# v0_5_0.net
KiCad netlist of a schematic drawn in EAGLE
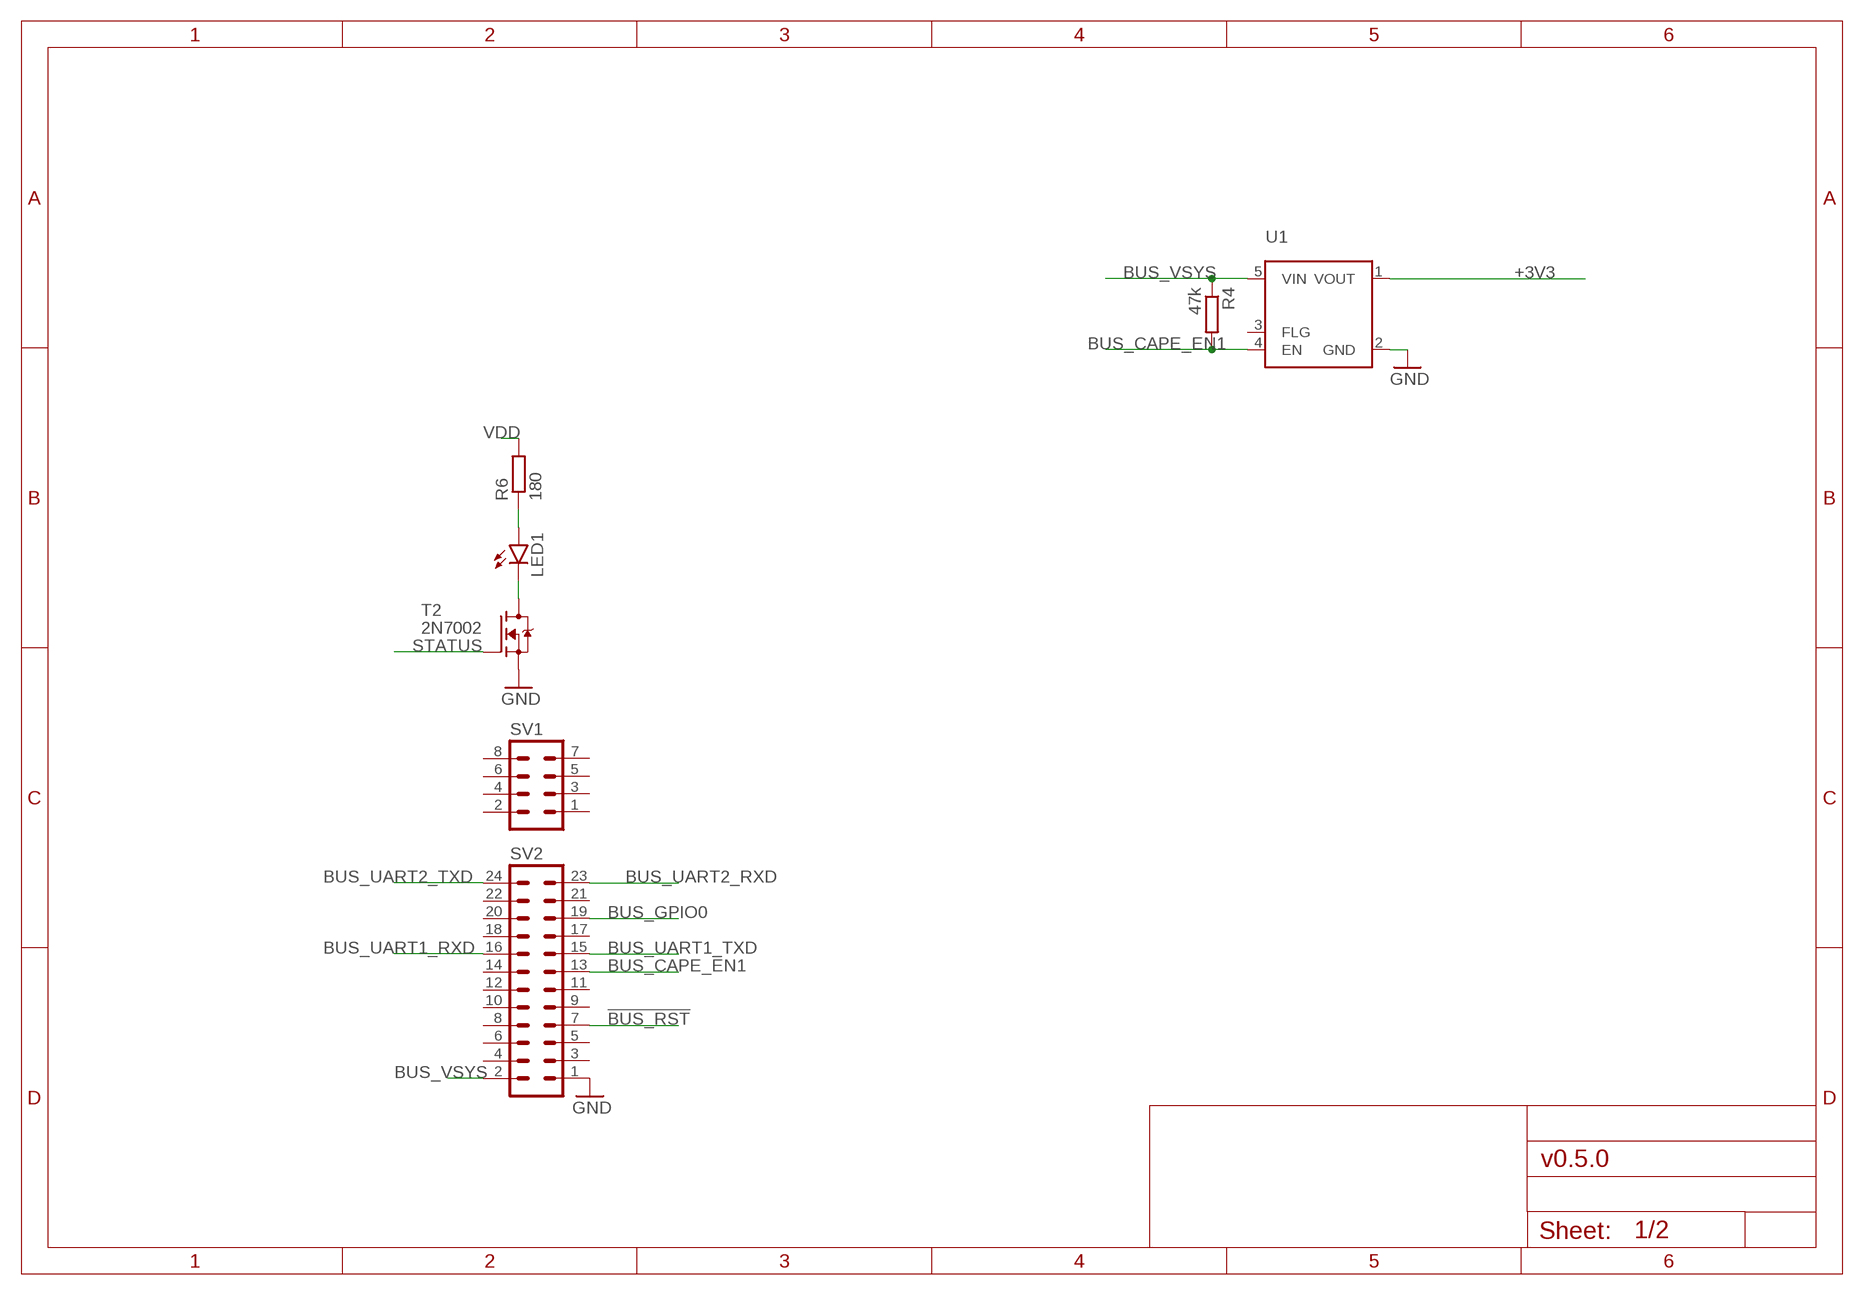
[diagram p0: schematic, sheet 1]
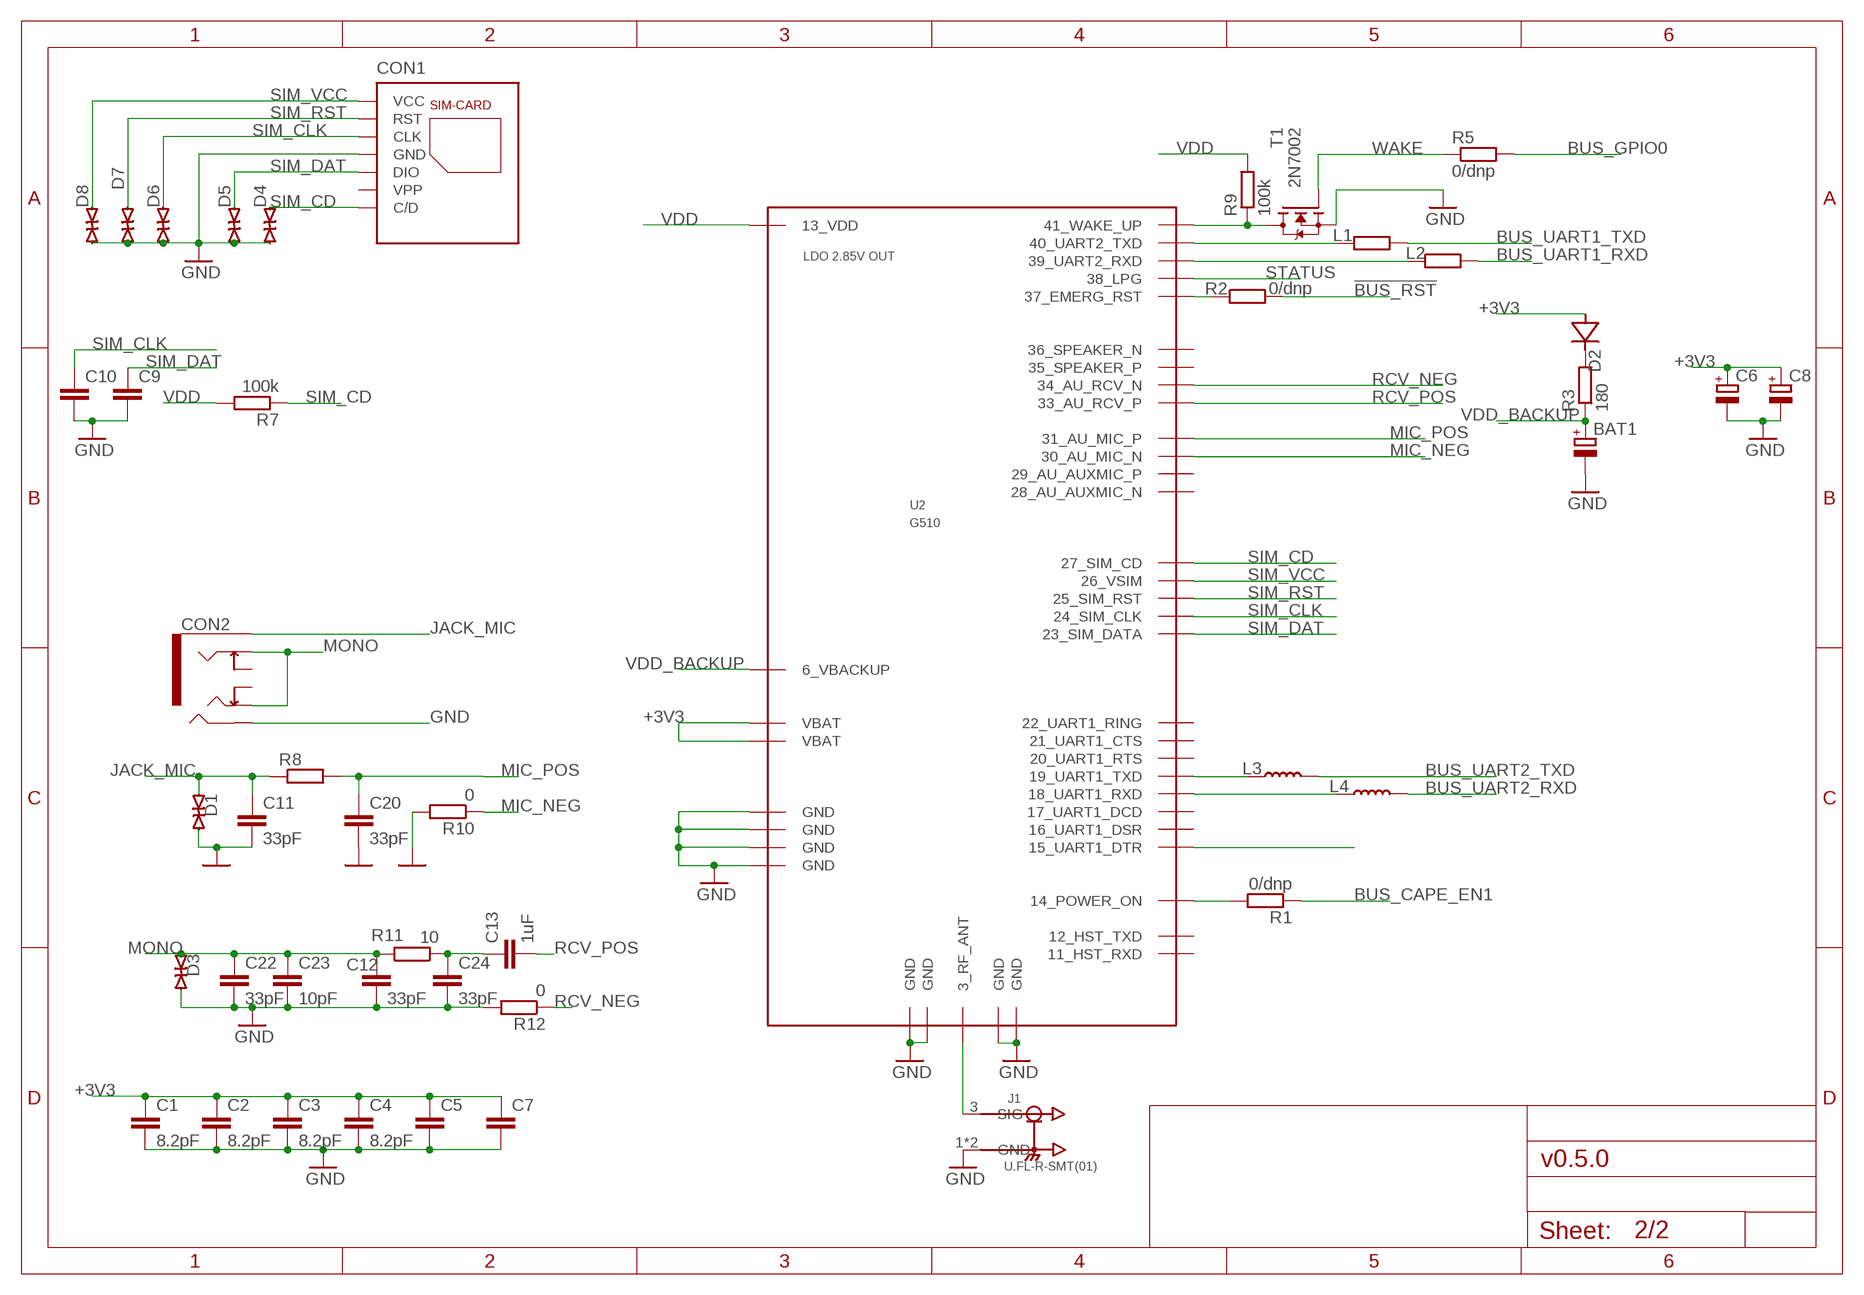
[diagram p1: schematic, sheet 2]

(export (version "E")
  (design (tool "Eeschema 10.0.6"))
  (components
    (comp (ref "LED1")
      (value "LEDCHIP-LED0603")
      (footprint "eagle-import:CHIP-LED0603")
      (libsource (lib "eagle-import") (part "LEDCHIP-LED0603"))
    )
    (comp (ref "R4")
      (value "47k")
      (footprint "eagle-import:R0402")
      (libsource (lib "eagle-import") (part "R-EU_R0402"))
    )
    (comp (ref "R6")
      (value "180")
      (footprint "eagle-import:R0402")
      (libsource (lib "eagle-import") (part "R-EU_R0402"))
    )
    (comp (ref "SV1")
      (value "MA04-2")
      (footprint "eagle-import:MA04-2")
      (libsource (lib "eagle-import") (part "MA04-2"))
    )
    (comp (ref "SV2")
      (value "MA12-2")
      (footprint "eagle-import:MA12-2")
      (libsource (lib "eagle-import") (part "MA12-2"))
    )
    (comp (ref "T2")
      (value "2N7002")
      (footprint "eagle-import:SOT95P240X110-3")
      (libsource (lib "eagle-import") (part "2N7002"))
    )
    (comp (ref "U1")
      (value "ap22802")
      (footprint "eagle-import:SOT25")
      (libsource (lib "eagle-import") (part "AP22802"))
    )
    (comp (ref "BAT1")
      (value "DCK-3R3E224U-E")
      (footprint "eagle-import:621")
      (libsource (lib "eagle-import") (part "DCK-3R3E224U-E"))
    )
    (comp (ref "C1")
      (value "8.2pF")
      (footprint "eagle-import:C0402K")
      (libsource (lib "eagle-import") (part "CAP-0402"))
    )
    (comp (ref "C2")
      (value "8.2pF")
      (footprint "eagle-import:C0402K")
      (libsource (lib "eagle-import") (part "CAP-0402"))
    )
    (comp (ref "C3")
      (value "8.2pF")
      (footprint "eagle-import:C0402K")
      (libsource (lib "eagle-import") (part "CAP-0402"))
    )
    (comp (ref "C4")
      (value "8.2pF")
      (footprint "eagle-import:C0402K")
      (libsource (lib "eagle-import") (part "CAP-0402"))
    )
    (comp (ref "C5")
      (value "C-EUC0603")
      (footprint "eagle-import:C0603")
      (libsource (lib "eagle-import") (part "C-EUC0603"))
    )
    (comp (ref "C6")
      (value "CAP-POL-SMC")
      (footprint "eagle-import:SMC_C")
      (libsource (lib "eagle-import") (part "CAP-POL-SMC"))
    )
    (comp (ref "C7")
      (value "C-EUC0603")
      (footprint "eagle-import:C0603")
      (libsource (lib "eagle-import") (part "C-EUC0603"))
    )
    (comp (ref "C8")
      (value "CAP-POL-SMC")
      (footprint "eagle-import:SMC_C")
      (libsource (lib "eagle-import") (part "CAP-POL-SMC"))
    )
    (comp (ref "C9")
      (value "CAP-0402")
      (footprint "eagle-import:C0402K")
      (libsource (lib "eagle-import") (part "CAP-0402"))
    )
    (comp (ref "C10")
      (value "CAP-0402")
      (footprint "eagle-import:C0402K")
      (libsource (lib "eagle-import") (part "CAP-0402"))
    )
    (comp (ref "C11")
      (value "33pF")
      (footprint "eagle-import:C0402K")
      (libsource (lib "eagle-import") (part "CAP-0402"))
    )
    (comp (ref "C12")
      (value "33pF")
      (footprint "eagle-import:C0402K")
      (libsource (lib "eagle-import") (part "CAP-0402"))
    )
    (comp (ref "C13")
      (value "1uF")
      (footprint "eagle-import:C0402K")
      (libsource (lib "eagle-import") (part "CAP-0402"))
    )
    (comp (ref "C20")
      (value "33pF")
      (footprint "eagle-import:C0402K")
      (libsource (lib "eagle-import") (part "CAP-0402"))
    )
    (comp (ref "C22")
      (value "33pF")
      (footprint "eagle-import:C0402K")
      (libsource (lib "eagle-import") (part "CAP-0402"))
    )
    (comp (ref "C23")
      (value "10pF")
      (footprint "eagle-import:C0402K")
      (libsource (lib "eagle-import") (part "CAP-0402"))
    )
    (comp (ref "C24")
      (value "33pF")
      (footprint "eagle-import:C0402K")
      (libsource (lib "eagle-import") (part "CAP-0402"))
    )
    (comp (ref "CON1")
      (value "115Q-BCA0")
      (footprint "eagle-import:115Q")
      (libsource (lib "eagle-import") (part "115Q-BCA0"))
    )
    (comp (ref "CON2")
      (value "1503-21")
      (footprint "eagle-import:150321")
      (libsource (lib "eagle-import") (part "1503-21"))
    )
    (comp (ref "D1")
      (value "ESD9B5.0ST5G")
      (footprint "eagle-import:SOD1006X40")
      (libsource (lib "eagle-import") (part "ESD9B5.0ST5G"))
    )
    (comp (ref "D2")
      (value "1N4148WS")
      (footprint "eagle-import:SOD323")
      (libsource (lib "eagle-import") (part "1N4148WS"))
    )
    (comp (ref "D3")
      (value "ESD9B5.0ST5G")
      (footprint "eagle-import:SOD1006X40")
      (libsource (lib "eagle-import") (part "ESD9B5.0ST5G"))
    )
    (comp (ref "D4")
      (value "ESD9B5.0ST5G")
      (footprint "eagle-import:SOD1006X40")
      (libsource (lib "eagle-import") (part "ESD9B5.0ST5G"))
    )
    (comp (ref "D5")
      (value "ESD9B5.0ST5G")
      (footprint "eagle-import:SOD1006X40")
      (libsource (lib "eagle-import") (part "ESD9B5.0ST5G"))
    )
    (comp (ref "D6")
      (value "ESD9B5.0ST5G")
      (footprint "eagle-import:SOD1006X40")
      (libsource (lib "eagle-import") (part "ESD9B5.0ST5G"))
    )
    (comp (ref "D7")
      (value "ESD9B5.0ST5G")
      (footprint "eagle-import:SOD1006X40")
      (libsource (lib "eagle-import") (part "ESD9B5.0ST5G"))
    )
    (comp (ref "D8")
      (value "ESD9B5.0ST5G")
      (footprint "eagle-import:SOD1006X40")
      (libsource (lib "eagle-import") (part "ESD9B5.0ST5G"))
    )
    (comp (ref "J1")
      (value "U.FL-R-SMT(01)")
      (footprint "eagle-import:HRS_U.FL-R-SMT(01)")
      (fields (field (name "MF") "Hirose") (field (name "MP") "U.FL-R-SMT_01_"))
      (libsource (lib "eagle-import") (part "U.FL-R-SMT(01)"))
    )
    (comp (ref "L1")
      (value "R-EU_R0402")
      (footprint "eagle-import:R0402")
      (libsource (lib "eagle-import") (part "R-EU_R0402"))
    )
    (comp (ref "L2")
      (value "R-EU_R0402")
      (footprint "eagle-import:R0402")
      (libsource (lib "eagle-import") (part "R-EU_R0402"))
    )
    (comp (ref "L3")
      (value "IND-0402")
      (footprint "eagle-import:L0402")
      (libsource (lib "eagle-import") (part "IND-0402"))
    )
    (comp (ref "L4")
      (value "IND-0402")
      (footprint "eagle-import:L0402")
      (libsource (lib "eagle-import") (part "IND-0402"))
    )
    (comp (ref "R1")
      (value "0/dnp")
      (footprint "eagle-import:R0402")
      (libsource (lib "eagle-import") (part "R-EU_R0402"))
    )
    (comp (ref "R2")
      (value "0/dnp")
      (footprint "eagle-import:R0402")
      (libsource (lib "eagle-import") (part "R-EU_R0402"))
    )
    (comp (ref "R3")
      (value "180")
      (footprint "eagle-import:R0402")
      (libsource (lib "eagle-import") (part "R-EU_R0402"))
    )
    (comp (ref "R5")
      (value "0/dnp")
      (footprint "eagle-import:R0402")
      (libsource (lib "eagle-import") (part "R-EU_R0402"))
    )
    (comp (ref "R7")
      (value "100k")
      (footprint "eagle-import:R0402")
      (libsource (lib "eagle-import") (part "R-EU_R0402"))
    )
    (comp (ref "R8")
      (value "R-EU_R0402")
      (footprint "eagle-import:R0402")
      (libsource (lib "eagle-import") (part "R-EU_R0402"))
    )
    (comp (ref "R9")
      (value "100k")
      (footprint "eagle-import:R0402")
      (libsource (lib "eagle-import") (part "R-EU_R0402"))
    )
    (comp (ref "R10")
      (value "0")
      (footprint "eagle-import:R0402")
      (libsource (lib "eagle-import") (part "R-EU_R0402"))
    )
    (comp (ref "R11")
      (value "10")
      (footprint "eagle-import:R0402")
      (libsource (lib "eagle-import") (part "R-EU_R0402"))
    )
    (comp (ref "R12")
      (value "0")
      (footprint "eagle-import:R0402")
      (libsource (lib "eagle-import") (part "R-EU_R0402"))
    )
    (comp (ref "T1")
      (value "2N7002")
      (footprint "eagle-import:SOT95P240X110-3")
      (libsource (lib "eagle-import") (part "2N7002"))
    )
    (comp (ref "U2")
      (value "G510")
      (footprint "eagle-import:G510")
      (libsource (lib "eagle-import") (part "G510"))
    )
  )
  (nets
    (net (code "1") (name "+3V3") (class "Default")
      (node (ref "C1") (pin "1") (pinfunction "1_1") (pintype "passive"))
      (node (ref "C2") (pin "1") (pinfunction "1_1") (pintype "passive"))
      (node (ref "C3") (pin "1") (pinfunction "1_1") (pintype "passive"))
      (node (ref "C4") (pin "1") (pinfunction "1_1") (pintype "passive"))
      (node (ref "C5") (pin "1") (pinfunction "1_1") (pintype "passive"))
      (node (ref "C6") (pin "+") (pinfunction "+_+") (pintype "passive"))
      (node (ref "C7") (pin "1") (pinfunction "1_1") (pintype "passive"))
      (node (ref "C8") (pin "+") (pinfunction "+_+") (pintype "passive"))
      (node (ref "D2") (pin "A") (pinfunction "A_A") (pintype "passive"))
      (node (ref "U1") (pin "1") (pinfunction "VOUT_1") (pintype "bidirectional"))
      (node (ref "U2") (pin "10_VBAT") (pinfunction "VBAT_10_VBAT") (pintype "power_in"))
      (node (ref "U2") (pin "9_VBAT") (pinfunction "VBAT_9_VBAT") (pintype "power_in"))
    )
    (net (code "2") (name "BUS_CAPE_EN1") (class "Default")
      (node (ref "R1") (pin "1") (pinfunction "1_1") (pintype "passive"))
      (node (ref "R4") (pin "2") (pinfunction "2_2") (pintype "passive"))
      (node (ref "SV2") (pin "13") (pinfunction "13_13") (pintype "passive"))
      (node (ref "U1") (pin "4") (pinfunction "EN_4") (pintype "bidirectional"))
    )
    (net (code "3") (name "BUS_GPIO0") (class "Default")
      (node (ref "R5") (pin "2") (pinfunction "2_2") (pintype "passive"))
      (node (ref "SV2") (pin "19") (pinfunction "19_19") (pintype "passive"))
    )
    (net (code "4") (name "BUS_UART1_RXD") (class "Default")
      (node (ref "L2") (pin "2") (pinfunction "2_2") (pintype "passive"))
      (node (ref "SV2") (pin "16") (pinfunction "16_16") (pintype "passive"))
    )
    (net (code "5") (name "BUS_UART1_TXD") (class "Default")
      (node (ref "L1") (pin "2") (pinfunction "2_2") (pintype "passive"))
      (node (ref "SV2") (pin "15") (pinfunction "15_15") (pintype "passive"))
    )
    (net (code "6") (name "BUS_UART2_RXD") (class "Default")
      (node (ref "L4") (pin "2") (pinfunction "2_2") (pintype "passive"))
      (node (ref "SV2") (pin "23") (pinfunction "23_23") (pintype "passive"))
    )
    (net (code "7") (name "BUS_UART2_TXD") (class "Default")
      (node (ref "L3") (pin "2") (pinfunction "2_2") (pintype "passive"))
      (node (ref "SV2") (pin "24") (pinfunction "24_24") (pintype "passive"))
    )
    (net (code "8") (name "BUS_VSYS") (class "Default")
      (node (ref "R4") (pin "1") (pinfunction "1_1") (pintype "passive"))
      (node (ref "SV2") (pin "2") (pinfunction "2_2") (pintype "passive"))
      (node (ref "U1") (pin "5") (pinfunction "VIN_5") (pintype "bidirectional"))
    )
    (net (code "9") (name "GND") (class "Default")
      (node (ref "BAT1") (pin "-") (pinfunction "-_-") (pintype "passive"))
      (node (ref "C1") (pin "2") (pinfunction "2_2") (pintype "passive"))
      (node (ref "C10") (pin "2") (pinfunction "2_2") (pintype "passive"))
      (node (ref "C11") (pin "2") (pinfunction "2_2") (pintype "passive"))
      (node (ref "C12") (pin "2") (pinfunction "2_2") (pintype "passive"))
      (node (ref "C2") (pin "2") (pinfunction "2_2") (pintype "passive"))
      (node (ref "C20") (pin "2") (pinfunction "2_2") (pintype "passive"))
      (node (ref "C22") (pin "2") (pinfunction "2_2") (pintype "passive"))
      (node (ref "C23") (pin "2") (pinfunction "2_2") (pintype "passive"))
      (node (ref "C24") (pin "2") (pinfunction "2_2") (pintype "passive"))
      (node (ref "C3") (pin "2") (pinfunction "2_2") (pintype "passive"))
      (node (ref "C4") (pin "2") (pinfunction "2_2") (pintype "passive"))
      (node (ref "C5") (pin "2") (pinfunction "2_2") (pintype "passive"))
      (node (ref "C6") (pin "-") (pinfunction "-_-") (pintype "passive"))
      (node (ref "C7") (pin "2") (pinfunction "2_2") (pintype "passive"))
      (node (ref "C8") (pin "-") (pinfunction "-_-") (pintype "passive"))
      (node (ref "C9") (pin "2") (pinfunction "2_2") (pintype "passive"))
      (node (ref "CON1") (pin "GND1") (pinfunction "GND_GND1") (pintype "passive"))
      (node (ref "CON1") (pin "GND2") (pinfunction "GND_GND2") (pintype "passive"))
      (node (ref "CON1") (pin "GND3") (pinfunction "GND_GND3") (pintype "passive"))
      (node (ref "CON1") (pin "GND4") (pinfunction "GND_GND4") (pintype "passive"))
      (node (ref "CON1") (pin "P5") (pinfunction "GND_P5") (pintype "passive"))
      (node (ref "CON2") (pin "2") (pinfunction "2_2") (pintype "bidirectional"))
      (node (ref "D1") (pin "2") (pinfunction "C_2") (pintype "passive"))
      (node (ref "D3") (pin "2") (pinfunction "C_2") (pintype "passive"))
      (node (ref "D4") (pin "1") (pinfunction "A_1") (pintype "passive"))
      (node (ref "D5") (pin "1") (pinfunction "A_1") (pintype "passive"))
      (node (ref "D6") (pin "1") (pinfunction "A_1") (pintype "passive"))
      (node (ref "D7") (pin "1") (pinfunction "A_1") (pintype "passive"))
      (node (ref "D8") (pin "1") (pinfunction "A_1") (pintype "passive"))
      (node (ref "J1") (pin "1") (pinfunction "GND_1") (pintype "passive"))
      (node (ref "J1") (pin "2") (pinfunction "GND_2") (pintype "passive"))
      (node (ref "R10") (pin "2") (pinfunction "2_2") (pintype "passive"))
      (node (ref "R12") (pin "2") (pinfunction "2_2") (pintype "passive"))
      (node (ref "SV2") (pin "1") (pinfunction "1_1") (pintype "passive"))
      (node (ref "T1") (pin "2") (pinfunction "S_2") (pintype "passive"))
      (node (ref "T2") (pin "2") (pinfunction "S_2") (pintype "passive"))
      (node (ref "U1") (pin "2") (pinfunction "GND_2") (pintype "bidirectional"))
      (node (ref "U2") (pin "1_GND") (pinfunction "GND_1_GND") (pintype "power_in"))
      (node (ref "U2") (pin "2_GND") (pinfunction "GND_2_GND") (pintype "power_in"))
      (node (ref "U2") (pin "32_GND") (pinfunction "GND_32_GND") (pintype "power_in"))
      (node (ref "U2") (pin "42_GND") (pinfunction "GND_42_GND") (pintype "power_in"))
      (node (ref "U2") (pin "4_GND") (pinfunction "GND_4_GND") (pintype "power_in"))
      (node (ref "U2") (pin "5_GND") (pinfunction "GND_5_GND") (pintype "power_in"))
      (node (ref "U2") (pin "7_GND") (pinfunction "GND_7_GND") (pintype "power_in"))
      (node (ref "U2") (pin "8_GND") (pinfunction "GND_8_GND") (pintype "power_in"))
    )
    (net (code "10") (name "JACK_MIC") (class "Default")
      (node (ref "C11") (pin "1") (pinfunction "1_1") (pintype "passive"))
      (node (ref "CON2") (pin "1") (pinfunction "1_1") (pintype "bidirectional"))
      (node (ref "D1") (pin "1") (pinfunction "A_1") (pintype "passive"))
      (node (ref "R8") (pin "1") (pinfunction "1_1") (pintype "passive"))
    )
    (net (code "11") (name "MIC_NEG") (class "Default")
      (node (ref "R10") (pin "1") (pinfunction "1_1") (pintype "passive"))
      (node (ref "U2") (pin "30_AU_MIC_N") (pinfunction "30_AU_MIC_N_30_AU_MIC_N") (pintype "bidirectional"))
    )
    (net (code "12") (name "MIC_POS") (class "Default")
      (node (ref "C20") (pin "1") (pinfunction "1_1") (pintype "passive"))
      (node (ref "R8") (pin "2") (pinfunction "2_2") (pintype "passive"))
      (node (ref "U2") (pin "31_AU_MIC_P") (pinfunction "31_AU_MIC_P_31_AU_MIC_P") (pintype "bidirectional"))
    )
    (net (code "13") (name "MONO") (class "Default")
      (node (ref "C12") (pin "1") (pinfunction "1_1") (pintype "passive"))
      (node (ref "C22") (pin "1") (pinfunction "1_1") (pintype "passive"))
      (node (ref "C23") (pin "1") (pinfunction "1_1") (pintype "passive"))
      (node (ref "CON2") (pin "3") (pinfunction "3_3") (pintype "bidirectional"))
      (node (ref "CON2") (pin "5") (pinfunction "5_5") (pintype "bidirectional"))
      (node (ref "D3") (pin "1") (pinfunction "A_1") (pintype "passive"))
      (node (ref "R11") (pin "2") (pinfunction "2_2") (pintype "passive"))
    )
    (net (code "14") (name "Net-(C13-Pad1)") (class "Default")
      (node (ref "C13") (pin "1") (pinfunction "1_1") (pintype "passive"))
      (node (ref "C24") (pin "1") (pinfunction "1_1") (pintype "passive"))
      (node (ref "R11") (pin "1") (pinfunction "1_1") (pintype "passive"))
    )
    (net (code "15") (name "Net-(D2-C)") (class "Default")
      (node (ref "D2") (pin "K") (pinfunction "C_K") (pintype "passive"))
      (node (ref "R3") (pin "2") (pinfunction "2_2") (pintype "passive"))
    )
    (net (code "16") (name "Net-(J1-SIG)") (class "Default")
      (node (ref "J1") (pin "3") (pinfunction "SIG_3") (pintype "passive"))
      (node (ref "U2") (pin "3_RF_ANT") (pinfunction "3_RF_ANT_3_RF_ANT") (pintype "bidirectional"))
    )
    (net (code "17") (name "Net-(L1-Pad1)") (class "Default")
      (node (ref "L1") (pin "1") (pinfunction "1_1") (pintype "passive"))
      (node (ref "U2") (pin "40_UART2_TXD") (pinfunction "40_UART2_TXD_40_UART2_TXD") (pintype "output"))
    )
    (net (code "18") (name "Net-(L2-Pad1)") (class "Default")
      (node (ref "L2") (pin "1") (pinfunction "1_1") (pintype "passive"))
      (node (ref "U2") (pin "39_UART2_RXD") (pinfunction "39_UART2_RXD_39_UART2_RXD") (pintype "input"))
    )
    (net (code "19") (name "Net-(L3-Pad1)") (class "Default")
      (node (ref "L3") (pin "1") (pinfunction "1_1") (pintype "passive"))
      (node (ref "U2") (pin "19_UART1_TXD") (pinfunction "19_UART1_TXD_19_UART1_TXD") (pintype "output"))
    )
    (net (code "20") (name "Net-(L4-Pad1)") (class "Default")
      (node (ref "L4") (pin "1") (pinfunction "1_1") (pintype "passive"))
      (node (ref "U2") (pin "18_UART1_RXD") (pinfunction "18_UART1_RXD_18_UART1_RXD") (pintype "input"))
    )
    (net (code "21") (name "Net-(LED1-PadA)") (class "Default")
      (node (ref "LED1") (pin "A") (pinfunction "A_A") (pintype "passive"))
      (node (ref "R6") (pin "1") (pinfunction "1_1") (pintype "passive"))
    )
    (net (code "22") (name "Net-(R1-Pad2)") (class "Default")
      (node (ref "R1") (pin "2") (pinfunction "2_2") (pintype "passive"))
      (node (ref "U2") (pin "14_POWER_ON") (pinfunction "14_POWER_ON_14_POWER_ON") (pintype "input"))
    )
    (net (code "23") (name "Net-(R2-Pad1)") (class "Default")
      (node (ref "R2") (pin "1") (pinfunction "1_1") (pintype "passive"))
      (node (ref "U2") (pin "37_EMERG_RST") (pinfunction "37_EMERG_RST_37_EMERG_RST") (pintype "input"))
    )
    (net (code "24") (name "Net-(T1-D)") (class "Default")
      (node (ref "R9") (pin "1") (pinfunction "1_1") (pintype "passive"))
      (node (ref "T1") (pin "3") (pinfunction "D_3") (pintype "passive"))
      (node (ref "U2") (pin "41_WAKE_UP") (pinfunction "41_WAKE_UP_41_WAKE_UP") (pintype "bidirectional"))
    )
    (net (code "25") (name "Net-(T2-D)") (class "Default")
      (node (ref "LED1") (pin "C") (pinfunction "C_C") (pintype "passive"))
      (node (ref "T2") (pin "3") (pinfunction "D_3") (pintype "passive"))
    )
    (net (code "26") (name "RCV_NEG") (class "Default")
      (node (ref "R12") (pin "1") (pinfunction "1_1") (pintype "passive"))
      (node (ref "U2") (pin "34_AU_RCV_N") (pinfunction "34_AU_RCV_N_34_AU_RCV_N") (pintype "bidirectional"))
    )
    (net (code "27") (name "RCV_POS") (class "Default")
      (node (ref "C13") (pin "2") (pinfunction "2_2") (pintype "passive"))
      (node (ref "U2") (pin "33_AU_RCV_P") (pinfunction "33_AU_RCV_P_33_AU_RCV_P") (pintype "bidirectional"))
    )
    (net (code "28") (name "SIM_CD") (class "Default")
      (node (ref "CON1") (pin "CD") (pinfunction "C/D_CD") (pintype "passive"))
      (node (ref "D4") (pin "2") (pinfunction "C_2") (pintype "passive"))
      (node (ref "R7") (pin "1") (pinfunction "1_1") (pintype "passive"))
      (node (ref "U2") (pin "27_SIM_CD") (pinfunction "27_SIM_CD_27_SIM_CD") (pintype "bidirectional"))
    )
    (net (code "29") (name "SIM_CLK") (class "Default")
      (node (ref "C10") (pin "1") (pinfunction "1_1") (pintype "passive"))
      (node (ref "CON1") (pin "P3") (pinfunction "CLK_P3") (pintype "passive"))
      (node (ref "D6") (pin "2") (pinfunction "C_2") (pintype "passive"))
      (node (ref "U2") (pin "24_SIM_CLK") (pinfunction "24_SIM_CLK_24_SIM_CLK") (pintype "bidirectional"))
    )
    (net (code "30") (name "SIM_DAT") (class "Default")
      (node (ref "C9") (pin "1") (pinfunction "1_1") (pintype "passive"))
      (node (ref "CON1") (pin "P7") (pinfunction "DIO_P7") (pintype "passive"))
      (node (ref "D5") (pin "2") (pinfunction "C_2") (pintype "passive"))
      (node (ref "U2") (pin "23_SIM_DATA") (pinfunction "23_SIM_DATA_23_SIM_DATA") (pintype "bidirectional"))
    )
    (net (code "31") (name "SIM_RST") (class "Default")
      (node (ref "CON1") (pin "P2") (pinfunction "RST_P2") (pintype "passive"))
      (node (ref "D7") (pin "2") (pinfunction "C_2") (pintype "passive"))
      (node (ref "U2") (pin "25_SIM_RST") (pinfunction "25_SIM_RST_25_SIM_RST") (pintype "bidirectional"))
    )
    (net (code "32") (name "SIM_VCC") (class "Default")
      (node (ref "CON1") (pin "P1") (pinfunction "VCC_P1") (pintype "passive"))
      (node (ref "D8") (pin "2") (pinfunction "C_2") (pintype "passive"))
      (node (ref "U2") (pin "26_VSIM") (pinfunction "26_VSIM_26_VSIM") (pintype "bidirectional"))
    )
    (net (code "33") (name "STATUS") (class "Default")
      (node (ref "T2") (pin "1") (pinfunction "G_1") (pintype "passive"))
      (node (ref "U2") (pin "38_LPG") (pinfunction "38_LPG_38_LPG") (pintype "output"))
    )
    (net (code "34") (name "VDD") (class "Default")
      (node (ref "R6") (pin "2") (pinfunction "2_2") (pintype "passive"))
      (node (ref "R7") (pin "2") (pinfunction "2_2") (pintype "passive"))
      (node (ref "R9") (pin "2") (pinfunction "2_2") (pintype "passive"))
      (node (ref "U2") (pin "13_VDD") (pinfunction "13_VDD_13_VDD") (pintype "power_in"))
    )
    (net (code "35") (name "VDD_BACKUP") (class "Default")
      (node (ref "BAT1") (pin "+") (pinfunction "+_+") (pintype "passive"))
      (node (ref "R3") (pin "1") (pinfunction "1_1") (pintype "passive"))
      (node (ref "U2") (pin "6_VBACKUP") (pinfunction "6_VBACKUP_6_VBACKUP") (pintype "power_in"))
    )
    (net (code "36") (name "WAKE") (class "Default")
      (node (ref "R5") (pin "1") (pinfunction "1_1") (pintype "passive"))
      (node (ref "T1") (pin "1") (pinfunction "G_1") (pintype "passive"))
    )
    (net (code "37") (name "unconnected-(CON1-VPP-PadP6)") (class "Default")
      (node (ref "CON1") (pin "P6") (pinfunction "VPP_P6") (pintype "passive"))
    )
    (net (code "38") (name "unconnected-(CON2-Pad4)") (class "Default")
      (node (ref "CON2") (pin "4") (pinfunction "4_4") (pintype "bidirectional"))
    )
    (net (code "39") (name "unconnected-(CON2-Pad6)") (class "Default")
      (node (ref "CON2") (pin "6") (pinfunction "6_6") (pintype "bidirectional"))
    )
    (net (code "40") (name "unconnected-(SV1-Pad1)") (class "Default")
      (node (ref "SV1") (pin "1") (pinfunction "1_1") (pintype "passive"))
    )
    (net (code "41") (name "unconnected-(SV1-Pad2)") (class "Default")
      (node (ref "SV1") (pin "2") (pinfunction "2_2") (pintype "passive"))
    )
    (net (code "42") (name "unconnected-(SV1-Pad3)") (class "Default")
      (node (ref "SV1") (pin "3") (pinfunction "3_3") (pintype "passive"))
    )
    (net (code "43") (name "unconnected-(SV1-Pad4)") (class "Default")
      (node (ref "SV1") (pin "4") (pinfunction "4_4") (pintype "passive"))
    )
    (net (code "44") (name "unconnected-(SV1-Pad5)") (class "Default")
      (node (ref "SV1") (pin "5") (pinfunction "5_5") (pintype "passive"))
    )
    (net (code "45") (name "unconnected-(SV1-Pad6)") (class "Default")
      (node (ref "SV1") (pin "6") (pinfunction "6_6") (pintype "passive"))
    )
    (net (code "46") (name "unconnected-(SV1-Pad7)") (class "Default")
      (node (ref "SV1") (pin "7") (pinfunction "7_7") (pintype "passive"))
    )
    (net (code "47") (name "unconnected-(SV1-Pad8)") (class "Default")
      (node (ref "SV1") (pin "8") (pinfunction "8_8") (pintype "passive"))
    )
    (net (code "48") (name "unconnected-(SV2-Pad3)") (class "Default")
      (node (ref "SV2") (pin "3") (pinfunction "3_3") (pintype "passive"))
    )
    (net (code "49") (name "unconnected-(SV2-Pad4)") (class "Default")
      (node (ref "SV2") (pin "4") (pinfunction "4_4") (pintype "passive"))
    )
    (net (code "50") (name "unconnected-(SV2-Pad5)") (class "Default")
      (node (ref "SV2") (pin "5") (pinfunction "5_5") (pintype "passive"))
    )
    (net (code "51") (name "unconnected-(SV2-Pad6)") (class "Default")
      (node (ref "SV2") (pin "6") (pinfunction "6_6") (pintype "passive"))
    )
    (net (code "52") (name "unconnected-(SV2-Pad8)") (class "Default")
      (node (ref "SV2") (pin "8") (pinfunction "8_8") (pintype "passive"))
    )
    (net (code "53") (name "unconnected-(SV2-Pad9)") (class "Default")
      (node (ref "SV2") (pin "9") (pinfunction "9_9") (pintype "passive"))
    )
    (net (code "54") (name "unconnected-(SV2-Pad10)") (class "Default")
      (node (ref "SV2") (pin "10") (pinfunction "10_10") (pintype "passive"))
    )
    (net (code "55") (name "unconnected-(SV2-Pad11)") (class "Default")
      (node (ref "SV2") (pin "11") (pinfunction "11_11") (pintype "passive"))
    )
    (net (code "56") (name "unconnected-(SV2-Pad12)") (class "Default")
      (node (ref "SV2") (pin "12") (pinfunction "12_12") (pintype "passive"))
    )
    (net (code "57") (name "unconnected-(SV2-Pad14)") (class "Default")
      (node (ref "SV2") (pin "14") (pinfunction "14_14") (pintype "passive"))
    )
    (net (code "58") (name "unconnected-(SV2-Pad17)") (class "Default")
      (node (ref "SV2") (pin "17") (pinfunction "17_17") (pintype "passive"))
    )
    (net (code "59") (name "unconnected-(SV2-Pad18)") (class "Default")
      (node (ref "SV2") (pin "18") (pinfunction "18_18") (pintype "passive"))
    )
    (net (code "60") (name "unconnected-(SV2-Pad20)") (class "Default")
      (node (ref "SV2") (pin "20") (pinfunction "20_20") (pintype "passive"))
    )
    (net (code "61") (name "unconnected-(SV2-Pad21)") (class "Default")
      (node (ref "SV2") (pin "21") (pinfunction "21_21") (pintype "passive"))
    )
    (net (code "62") (name "unconnected-(SV2-Pad22)") (class "Default")
      (node (ref "SV2") (pin "22") (pinfunction "22_22") (pintype "passive"))
    )
    (net (code "63") (name "unconnected-(U1-FLG-Pad3)") (class "Default")
      (node (ref "U1") (pin "3") (pinfunction "FLG_3") (pintype "bidirectional"))
    )
    (net (code "64") (name "unconnected-(U2-11_HST_RXD-Pad11_HSTRXD)") (class "Default")
      (node (ref "U2") (pin "11_HSTRXD") (pinfunction "11_HST_RXD_11_HSTRXD") (pintype "input"))
    )
    (net (code "65") (name "unconnected-(U2-Pad12_HST_TXD)") (class "Default")
      (node (ref "U2") (pin "12_HST_TXD") (pinfunction "12_HST_TXD_12_HST_TXD") (pintype "output"))
    )
    (net (code "66") (name "unconnected-(U2-Pad15_UART1_DTR)") (class "Default")
      (node (ref "U2") (pin "15_UART1_DTR") (pinfunction "15_UART1_DTR_15_UART1_DTR") (pintype "bidirectional"))
    )
    (net (code "67") (name "unconnected-(U2-Pad16_UART1_DSR)") (class "Default")
      (node (ref "U2") (pin "16_UART1_DSR") (pinfunction "16_UART1_DSR_16_UART1_DSR") (pintype "bidirectional"))
    )
    (net (code "68") (name "unconnected-(U2-Pad17_UART1_DCD)") (class "Default")
      (node (ref "U2") (pin "17_UART1_DCD") (pinfunction "17_UART1_DCD_17_UART1_DCD") (pintype "bidirectional"))
    )
    (net (code "69") (name "unconnected-(U2-Pad20_UART1_RTS)") (class "Default")
      (node (ref "U2") (pin "20_UART1_RTS") (pinfunction "20_UART1_RTS_20_UART1_RTS") (pintype "bidirectional"))
    )
    (net (code "70") (name "unconnected-(U2-Pad21_UART1_CTS)") (class "Default")
      (node (ref "U2") (pin "21_UART1_CTS") (pinfunction "21_UART1_CTS_21_UART1_CTS") (pintype "bidirectional"))
    )
    (net (code "71") (name "unconnected-(U2-Pad22_UART1_RING)") (class "Default")
      (node (ref "U2") (pin "22_UART1_RING") (pinfunction "22_UART1_RING_22_UART1_RING") (pintype "bidirectional"))
    )
    (net (code "72") (name "unconnected-(U2-Pad28_AU_AUXMIC_N)") (class "Default")
      (node (ref "U2") (pin "28_AU_AUXMIC_N") (pinfunction "28_AU_AUXMIC_N_28_AU_AUXMIC_N") (pintype "bidirectional"))
    )
    (net (code "73") (name "unconnected-(U2-Pad29_AU_AUXMIC_P)") (class "Default")
      (node (ref "U2") (pin "29_AU_AUXMIC_P") (pinfunction "29_AU_AUXMIC_P_29_AU_AUXMIC_P") (pintype "bidirectional"))
    )
    (net (code "74") (name "unconnected-(U2-Pad35_SPEAKER_P)") (class "Default")
      (node (ref "U2") (pin "35_SPEAKER_P") (pinfunction "35_SPEAKER_P_35_SPEAKER_P") (pintype "bidirectional"))
    )
    (net (code "75") (name "unconnected-(U2-Pad36_SPEAKER_N)") (class "Default")
      (node (ref "U2") (pin "36_SPEAKER_N") (pinfunction "36_SPEAKER_N_36_SPEAKER_N") (pintype "bidirectional"))
    )
    (net (code "76") (name "~{BUS_RST}") (class "Default")
      (node (ref "R2") (pin "2") (pinfunction "2_2") (pintype "passive"))
      (node (ref "SV2") (pin "7") (pinfunction "7_7") (pintype "passive"))
    )
  )
)
